# 48V-24V_Buck_Converter.net
KiCad netlist of a schematic drawn in Altium Designer
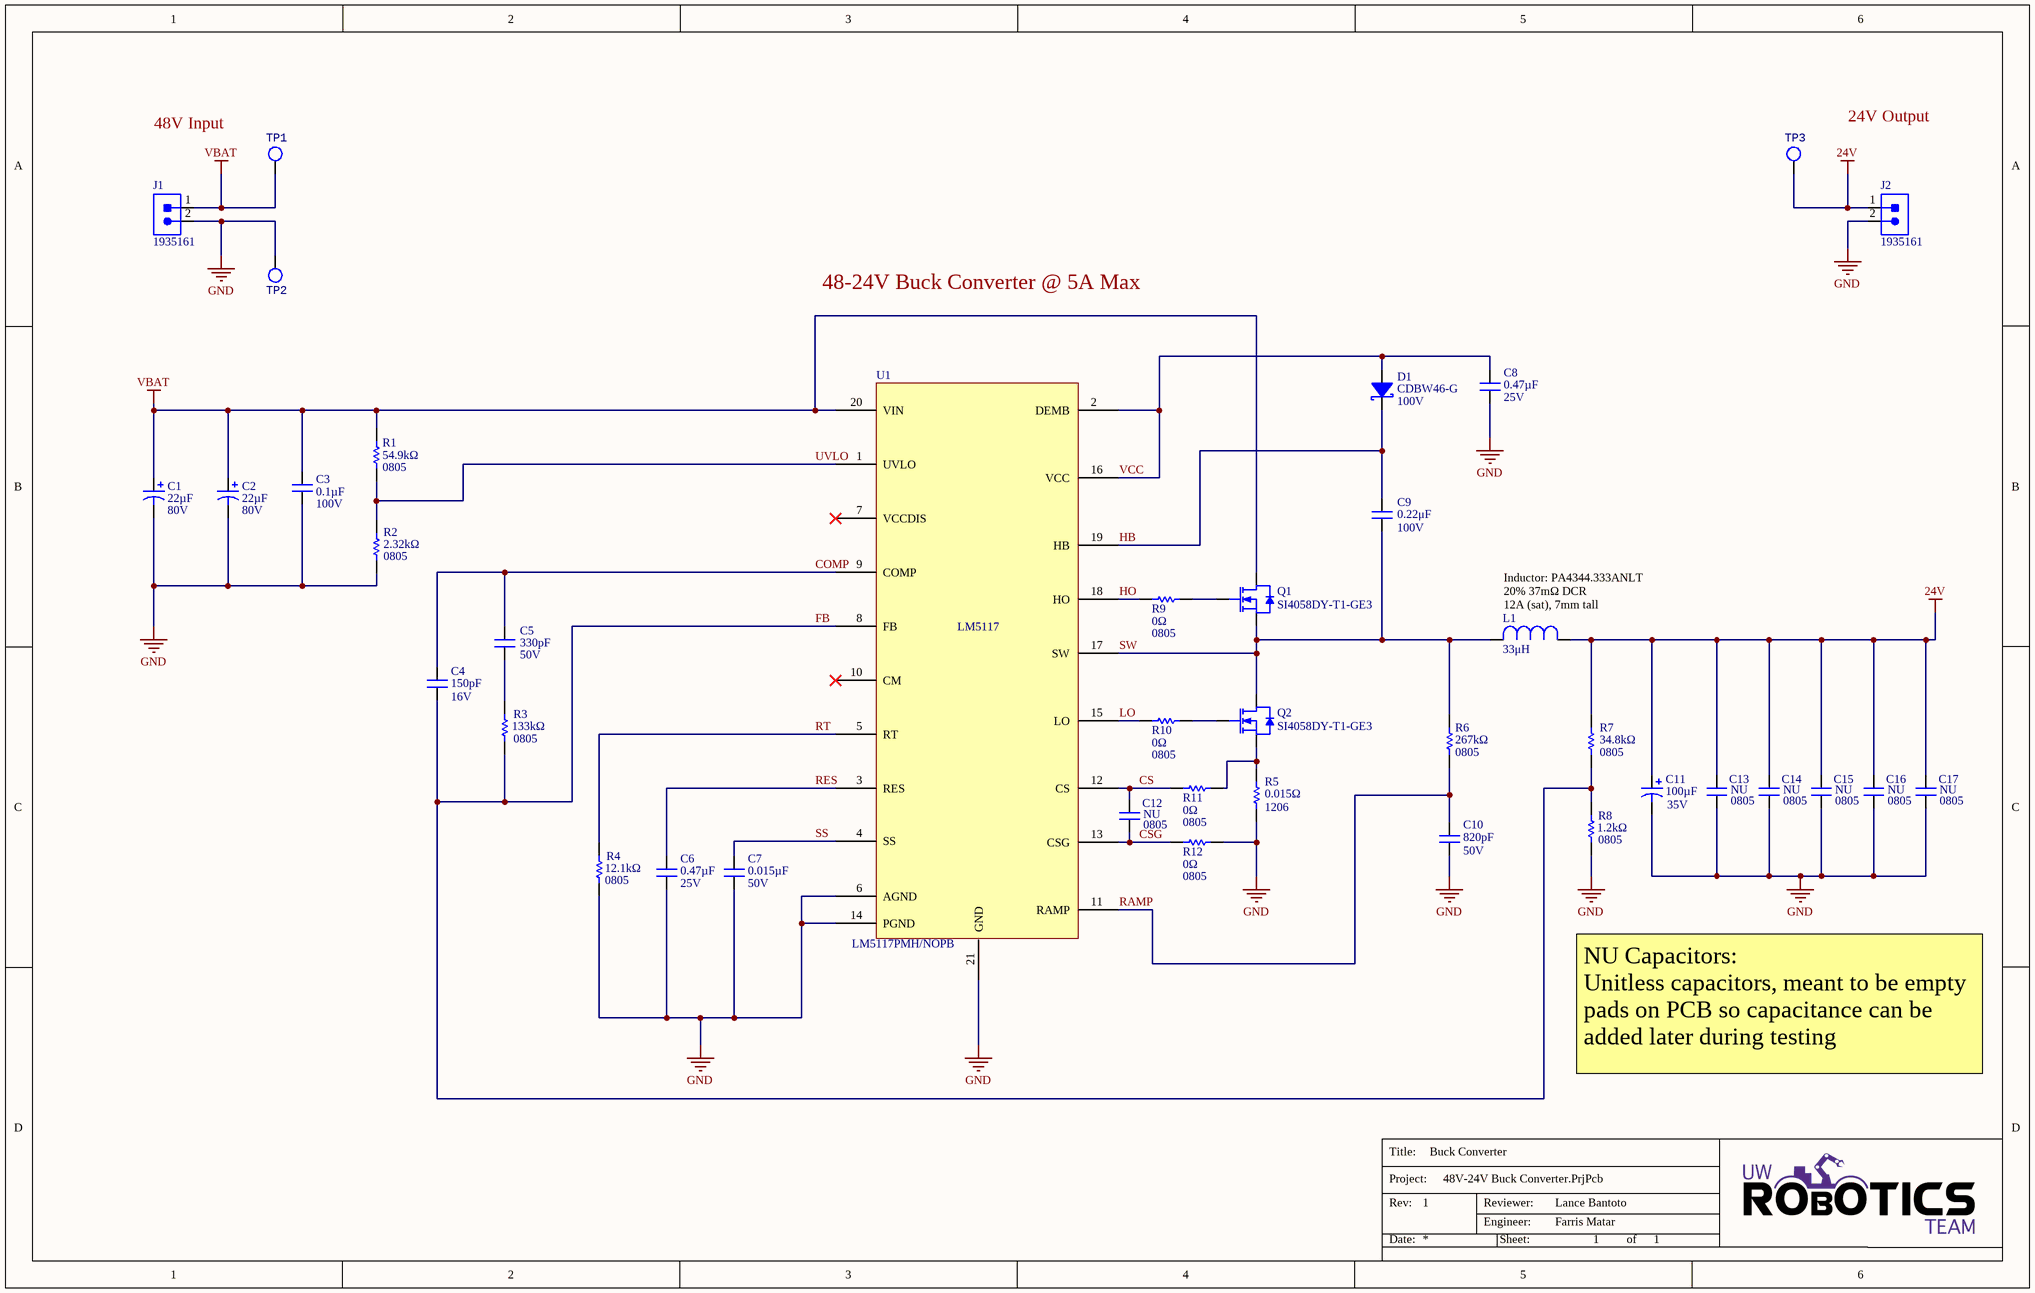
[diagram p0: 48V-24V Buck Converter.SchDoc]

(export (version "E")
  (design (tool "Eeschema 10.0.6"))
  (components
    (comp (ref "C1")
      (value "22µF")
      (footprint "RADIAL_KEMET_KN")
      (description "CAP ALUM POLY 22UF 20% 80V SMD")
      (fields (field (name "VOLTAGE RATING") "80V") (field (name "Comment") "CAP_22uF_80V_ALUM"))
      (libsource (lib "UWRT_Schematic_Library_2020") (part "CAP_22uF_80V_ALUM"))
    )
    (comp (ref "C2")
      (value "22µF")
      (footprint "RADIAL_KEMET_KN")
      (description "CAP ALUM POLY 22UF 20% 80V SMD")
      (fields (field (name "VOLTAGE RATING") "80V") (field (name "Comment") "CAP_22uF_80V_ALUM"))
      (libsource (lib "UWRT_Schematic_Library_2020") (part "CAP_22uF_80V_ALUM"))
    )
    (comp (ref "C3")
      (value "0.1µF")
      (footprint "CAP0805")
      (description "CAP CER 0.1UF 100V X7R 0805")
      (fields (field (name "VOLTAGE RATING") "100V") (field (name "Comment") "CAP_0.1uF_100V_0805"))
      (libsource (lib "UWRT_Schematic_Library_2020") (part "CAP_0.1uF_100V_0805"))
    )
    (comp (ref "C4")
      (value "150pF")
      (footprint "CAP0805")
      (description "CAP CER 150PF 16V X7R 0805")
      (fields (field (name "VOLTAGE RATING") "16V") (field (name "Comment") "CAP_150pF_16V_0805"))
      (libsource (lib "UWRT_Schematic_Library_2020") (part "CAP_150pF_16V_0805"))
    )
    (comp (ref "C5")
      (value "330pF")
      (footprint "CAP0805")
      (description "CAP CER 330PF 50V C0G/NPO 0805")
      (fields (field (name "VOLTAGE RATING") "50V") (field (name "Comment") "CAP_330pF_50V_0805"))
      (libsource (lib "UWRT_Schematic_Library_2020") (part "CAP_330pF_50V_0805"))
    )
    (comp (ref "C6")
      (value "0.47µF")
      (footprint "CAP0805")
      (description "CAP CER 0.47UF 25V X5R 0805")
      (fields (field (name "VOLTAGE RATING") "25V") (field (name "Comment") "CAP_0.47uF_25V_0805"))
      (libsource (lib "UWRT_Schematic_Library_2020") (part "CAP_0.47uF_25V_0805"))
    )
    (comp (ref "C7")
      (value "0.015µF")
      (footprint "CAP0805")
      (description "CAP CER 0.015UF 50V C0G 0805")
      (fields (field (name "VOLTAGE RATING") "50V") (field (name "Comment") "CAP_0.015uF_50V_0805"))
      (libsource (lib "UWRT_Schematic_Library_2020") (part "CAP_0.015uF_50V_0805"))
    )
    (comp (ref "C8")
      (value "0.47µF")
      (footprint "CAP0805")
      (description "CAP CER 0.47UF 25V X5R 0805")
      (fields (field (name "VOLTAGE RATING") "25V") (field (name "Comment") "CAP_0.47uF_25V_0805"))
      (libsource (lib "UWRT_Schematic_Library_2020") (part "CAP_0.47uF_25V_0805"))
    )
    (comp (ref "C9")
      (value "0.22μF")
      (footprint "CAP2012")
      (description "CAP CER 0.22UF 100V X7R 0805")
      (fields (field (name "VOLTAGE RATING") "100V") (field (name "Comment") "CAP_0.22uF_100V_0805"))
      (libsource (lib "UWRT_Schematic_Library_2020") (part "CAP_0.22uF_100V_0805"))
    )
    (comp (ref "C10")
      (value "820pF")
      (footprint "CAP0805")
      (description "CAP CER 820PF 50V C0G/NP0 0805")
      (fields (field (name "VOLTAGE RATING") "50V") (field (name "Comment") "CAP_820pF_50V_0805"))
      (libsource (lib "UWRT_Schematic_Library_2020") (part "CAP_820pF_50V_0805"))
    )
    (comp (ref "C11")
      (value "100µF")
      (footprint "RADIAL_CORNELL_D")
      (description "CAP ALUM 100UF 20% 35V SMD")
      (fields (field (name "VOLTAGE RATING") "35V") (field (name "Comment") "CAP_100uF_35V_ALUM"))
      (libsource (lib "UWRT_Schematic_Library_2020") (part "CAP_100uF_35V_ALUM"))
    )
    (comp (ref "C12")
      (value "NU")
      (footprint "CAP0805")
      (description "PLACEHOLDER CAPACITOR 0805")
      (fields (field (name "PACKAGE/FOOTPRINT") "0805") (field (name "Comment") "CAP_NU_0805"))
      (libsource (lib "UWRT_Schematic_Library_2020") (part "CAP_NU_0805"))
    )
    (comp (ref "C13")
      (value "NU")
      (footprint "CAP0805")
      (description "PLACEHOLDER CAPACITOR 0805")
      (fields (field (name "PACKAGE/FOOTPRINT") "0805") (field (name "Comment") "CAP_NU_0805"))
      (libsource (lib "UWRT_Schematic_Library_2020") (part "CAP_NU_0805"))
    )
    (comp (ref "C14")
      (value "NU")
      (footprint "CAP0805")
      (description "PLACEHOLDER CAPACITOR 0805")
      (fields (field (name "PACKAGE/FOOTPRINT") "0805") (field (name "Comment") "CAP_NU_0805"))
      (libsource (lib "UWRT_Schematic_Library_2020") (part "CAP_NU_0805"))
    )
    (comp (ref "C15")
      (value "NU")
      (footprint "CAP0805")
      (description "PLACEHOLDER CAPACITOR 0805")
      (fields (field (name "PACKAGE/FOOTPRINT") "0805") (field (name "Comment") "CAP_NU_0805"))
      (libsource (lib "UWRT_Schematic_Library_2020") (part "CAP_NU_0805"))
    )
    (comp (ref "C16")
      (value "NU")
      (footprint "CAP0805")
      (description "PLACEHOLDER CAPACITOR 0805")
      (fields (field (name "PACKAGE/FOOTPRINT") "0805") (field (name "Comment") "CAP_NU_0805"))
      (libsource (lib "UWRT_Schematic_Library_2020") (part "CAP_NU_0805"))
    )
    (comp (ref "C17")
      (value "NU")
      (footprint "CAP0805")
      (description "PLACEHOLDER CAPACITOR 0805")
      (fields (field (name "PACKAGE/FOOTPRINT") "0805") (field (name "Comment") "CAP_NU_0805"))
      (libsource (lib "UWRT_Schematic_Library_2020") (part "CAP_NU_0805"))
    )
    (comp (ref "D1")
      (value "DIO_SCHOTTKY_100V_150mA")
      (footprint "SOD-123_FLAT")
      (description "DIODE SCHOTTKY 100V 150MA SOD123")
      (fields (field (name "MANUFACTURER PART NUMBER 1") "CDBW46-G") (field (name "VR (MAX)") "100V"))
      (libsource (lib "UWRT_Schematic_Library_2020") (part "DIO_SCHOTTKY_100V_150mA"))
    )
    (comp (ref "J1")
      (value "CON_2POS_SCREW_TERM")
      (footprint "1935161")
      (description "TERM BLK 2POS SIDE ENTRY 5MM")
      (fields (field (name "MANUFACTURER PART NUMBER 1") "1935161"))
      (libsource (lib "UWRT_Schematic_Library_2020") (part "CON_2POS_SCREW_TERM"))
    )
    (comp (ref "J2")
      (value "CON_2POS_SCREW_TERM")
      (footprint "1935161")
      (description "TERM BLK 2POS SIDE ENTRY 5MM")
      (fields (field (name "MANUFACTURER PART NUMBER 1") "1935161"))
      (libsource (lib "") (part "CON_2POS_SCREW_TERM_1"))
    )
    (comp (ref "L1")
      (value "IND_33uH_12.0A")
      (footprint "IND_PULSE_PA4344")
      (description "FIXED IND 33UH 12A 37 MOHM SMD")
      (fields (field (name "INDUCTANCE") "33μH"))
      (libsource (lib "UWRT_Schematic_Library_2020") (part "IND_33uH_12.0A"))
    )
    (comp (ref "Q1")
      (value "NMOS_100V_10.3A")
      (footprint "8-SOIC_NMOS")
      (description "MOSFET N-CH 100V 10.3A 8SOIC")
      (fields (field (name "MANUFACTURER PART NUMBER 1") "SI4058DY-T1-GE3"))
      (libsource (lib "UWRT_Schematic_Library_2020") (part "NMOS_100V_10.3A"))
    )
    (comp (ref "Q2")
      (value "NMOS_100V_10.3A")
      (footprint "8-SOIC_NMOS")
      (description "MOSFET N-CH 100V 10.3A 8SOIC")
      (fields (field (name "MANUFACTURER PART NUMBER 1") "SI4058DY-T1-GE3"))
      (libsource (lib "UWRT_Schematic_Library_2020") (part "NMOS_100V_10.3A"))
    )
    (comp (ref "R1")
      (value "54.9kΩ")
      (footprint "RES0805")
      (description "RES SMD 54.9K OHM 1% 1/8W 0805")
      (fields (field (name "PACKAGE/FOOTPRINT") "0805") (field (name "Comment") "RES_54.9kΩ_0805_1%"))
      (libsource (lib "UWRT_Schematic_Library_2020") (part "RES_54.9kΩ_0805_1%"))
    )
    (comp (ref "R2")
      (value "2.32kΩ")
      (footprint "RES0805")
      (description "RES 2.32K OHM 1% 1/4W 0805")
      (fields (field (name "PACKAGE/FOOTPRINT") "0805") (field (name "Comment") "RES_2.32kΩ_0805_1%"))
      (libsource (lib "UWRT_Schematic_Library_2020") (part "RES_2.32kΩ_0805_1%"))
    )
    (comp (ref "R3")
      (value "133kΩ")
      (footprint "RES0805")
      (description "RES SMD 133K OHM 1% 1/8W 0805")
      (fields (field (name "PACKAGE/FOOTPRINT") "0805") (field (name "Comment") "RES_133kΩ_0805_1%"))
      (libsource (lib "UWRT_Schematic_Library_2020") (part "RES_133kΩ_0805_1%"))
    )
    (comp (ref "R4")
      (value "12.1kΩ")
      (footprint "RES0805")
      (description "RES 12.1K OHM 1% 1/4W 0805")
      (fields (field (name "PACKAGE/FOOTPRINT") "0805") (field (name "Comment") "RES_12.1kΩ_0805_1%"))
      (libsource (lib "UWRT_Schematic_Library_2020") (part "RES_12.1kΩ_0805_1%"))
    )
    (comp (ref "R5")
      (value "0.015Ω")
      (footprint "RES1206")
      (description "RES 0.015 OHM 1% 1/2W 1206")
      (fields (field (name "PACKAGE/FOOTPRINT") "1206") (field (name "Comment") "RES_0.015Ω_1206_1%"))
      (libsource (lib "UWRT_Schematic_Library_2020") (part "RES_0.015Ω_1206_1%"))
    )
    (comp (ref "R6")
      (value "267kΩ")
      (footprint "RES0805")
      (description "RES SMD 267K OHM 1% 1/8W 0805")
      (fields (field (name "PACKAGE/FOOTPRINT") "0805") (field (name "Comment") "RES_267kΩ_0805_1%"))
      (libsource (lib "UWRT_Schematic_Library_2020") (part "RES_267kΩ_0805_1%"))
    )
    (comp (ref "R7")
      (value "34.8kΩ")
      (footprint "RES0805")
      (description "RES 34.8K OHM 1% 1/8W 0805")
      (fields (field (name "PACKAGE/FOOTPRINT") "0805") (field (name "Comment") "RES_34.8kΩ_0805_1%"))
      (libsource (lib "UWRT_Schematic_Library_2020") (part "RES_34.8kΩ_0805_1%"))
    )
    (comp (ref "R8")
      (value "1.2kΩ")
      (footprint "RES0805")
      (description "RES SMD 1.2K OHM 1% 1/8W 0805")
      (fields (field (name "PACKAGE/FOOTPRINT") "0805") (field (name "Comment") "RES_1.2kΩ_0805"))
      (libsource (lib "UWRT_Schematic_Library_2020") (part "RES_1.2kΩ_0805_1%"))
    )
    (comp (ref "R9")
      (value "0Ω")
      (footprint "RES0805")
      (description "RES 0 OHM JUMPER 1/8W 0805")
      (fields
        (field (name "PACKAGE/FOOTPRINT") "0805")
        (field (name "LCSC PART #") "C17477")
        (field (name "Comment") "RES_0Ω_0805")
      )
      (libsource (lib "UWRT_Schematic_Library_2020") (part "RES_0Ω_0805"))
    )
    (comp (ref "R10")
      (value "0Ω")
      (footprint "RES0805")
      (description "RES 0 OHM JUMPER 1/8W 0805")
      (fields
        (field (name "PACKAGE/FOOTPRINT") "0805")
        (field (name "LCSC PART #") "C17477")
        (field (name "Comment") "RES_0Ω_0805")
      )
      (libsource (lib "UWRT_Schematic_Library_2020") (part "RES_0Ω_0805"))
    )
    (comp (ref "R11")
      (value "0Ω")
      (footprint "RES0805")
      (description "RES 0 OHM JUMPER 1/8W 0805")
      (fields
        (field (name "PACKAGE/FOOTPRINT") "0805")
        (field (name "LCSC PART #") "C17477")
        (field (name "Comment") "RES_0Ω_0805")
      )
      (libsource (lib "UWRT_Schematic_Library_2020") (part "RES_0Ω_0805"))
    )
    (comp (ref "R12")
      (value "0Ω")
      (footprint "RES0805")
      (description "RES 0 OHM JUMPER 1/8W 0805")
      (fields
        (field (name "PACKAGE/FOOTPRINT") "0805")
        (field (name "LCSC PART #") "C17477")
        (field (name "Comment") "RES_0Ω_0805")
      )
      (libsource (lib "UWRT_Schematic_Library_2020") (part "RES_0Ω_0805"))
    )
    (comp (ref "TP1")
      (value "TESTPOINT_LOOP")
      (footprint "TESTPOINT_LOOP")
      (description "TESTPOINT THRUHOLE")
      (libsource (lib "UWRT_Schematic_Library_2020") (part "TESTPOINT_LOOP"))
    )
    (comp (ref "TP2")
      (value "TESTPOINT_LOOP")
      (footprint "TESTPOINT_LOOP")
      (description "TESTPOINT THRUHOLE")
      (libsource (lib "UWRT_Schematic_Library_2020") (part "TESTPOINT_LOOP"))
    )
    (comp (ref "TP3")
      (value "TESTPOINT_LOOP")
      (footprint "TESTPOINT_LOOP")
      (description "TESTPOINT THRUHOLE")
      (libsource (lib "UWRT_Schematic_Library_2020") (part "TESTPOINT_LOOP"))
    )
    (comp (ref "U1")
      (value "BUCK_LM5117PWP")
      (footprint "HTSSOP")
      (description "IC REG CTRLR BUCK 20TSSOP")
      (fields (field (name "MANUFACTURER PART NUMBER 1") "LM5117PMH/NOPB"))
      (libsource (lib "UWRT_Schematic_Library_2020") (part "BUCK_LM5117PWP"))
    )
  )
  (nets
    (net (code "1") (name "/COMP") (class "Default")
      (node (ref "C4") (pin "2") (pinfunction "2_2") (pintype "passive"))
      (node (ref "C5") (pin "2") (pinfunction "2_2") (pintype "passive"))
      (node (ref "U1") (pin "9") (pinfunction "COMP_9") (pintype "passive"))
    )
    (net (code "2") (name "/CS") (class "Default")
      (node (ref "C12") (pin "2") (pinfunction "2_2") (pintype "passive"))
      (node (ref "R11") (pin "1") (pinfunction "1_1") (pintype "passive"))
      (node (ref "U1") (pin "12") (pinfunction "CS_12") (pintype "passive"))
    )
    (net (code "3") (name "/CSG") (class "Default")
      (node (ref "C12") (pin "1") (pinfunction "1_1") (pintype "passive"))
      (node (ref "R12") (pin "1") (pinfunction "1_1") (pintype "passive"))
      (node (ref "U1") (pin "13") (pinfunction "CSG_13") (pintype "passive"))
    )
    (net (code "4") (name "/FB") (class "Default")
      (node (ref "C4") (pin "1") (pinfunction "1_1") (pintype "passive"))
      (node (ref "R3") (pin "1") (pinfunction "1_1") (pintype "passive"))
      (node (ref "R7") (pin "1") (pinfunction "1_1") (pintype "passive"))
      (node (ref "R8") (pin "2") (pinfunction "2_2") (pintype "passive"))
      (node (ref "U1") (pin "8") (pinfunction "FB_8") (pintype "passive"))
    )
    (net (code "5") (name "/HB") (class "Default")
      (node (ref "C9") (pin "2") (pinfunction "2_2") (pintype "passive"))
      (node (ref "D1") (pin "2") (pinfunction "Cathode_2") (pintype "passive"))
      (node (ref "U1") (pin "19") (pinfunction "HB_19") (pintype "passive"))
    )
    (net (code "6") (name "/HO") (class "Default")
      (node (ref "R9") (pin "1") (pinfunction "1_1") (pintype "passive"))
      (node (ref "U1") (pin "18") (pinfunction "HO_18") (pintype "passive"))
    )
    (net (code "7") (name "/LO") (class "Default")
      (node (ref "R10") (pin "1") (pinfunction "1_1") (pintype "passive"))
      (node (ref "U1") (pin "15") (pinfunction "LO_15") (pintype "passive"))
    )
    (net (code "8") (name "/RAMP") (class "Default")
      (node (ref "C10") (pin "2") (pinfunction "2_2") (pintype "passive"))
      (node (ref "R6") (pin "1") (pinfunction "1_1") (pintype "passive"))
      (node (ref "U1") (pin "11") (pinfunction "RAMP_11") (pintype "passive"))
    )
    (net (code "9") (name "/RES") (class "Default")
      (node (ref "C6") (pin "2") (pinfunction "2_2") (pintype "passive"))
      (node (ref "U1") (pin "3") (pinfunction "RES_3") (pintype "passive"))
    )
    (net (code "10") (name "/RT") (class "Default")
      (node (ref "R4") (pin "2") (pinfunction "2_2") (pintype "passive"))
      (node (ref "U1") (pin "5") (pinfunction "RT_5") (pintype "passive"))
    )
    (net (code "11") (name "/SS") (class "Default")
      (node (ref "C7") (pin "2") (pinfunction "2_2") (pintype "passive"))
      (node (ref "U1") (pin "4") (pinfunction "SS_4") (pintype "passive"))
    )
    (net (code "12") (name "/SW") (class "Default")
      (node (ref "C9") (pin "1") (pinfunction "1_1") (pintype "passive"))
      (node (ref "L1") (pin "2") (pinfunction "2_2") (pintype "passive"))
      (node (ref "Q1") (pin "2") (pinfunction "Source_2") (pintype "passive"))
      (node (ref "Q2") (pin "3") (pinfunction "Drain_3") (pintype "passive"))
      (node (ref "R6") (pin "2") (pinfunction "2_2") (pintype "passive"))
      (node (ref "U1") (pin "17") (pinfunction "SW_17") (pintype "passive"))
    )
    (net (code "13") (name "/UVLO") (class "Default")
      (node (ref "R1") (pin "1") (pinfunction "1_1") (pintype "passive"))
      (node (ref "R2") (pin "2") (pinfunction "2_2") (pintype "passive"))
      (node (ref "U1") (pin "1") (pinfunction "UVLO_1") (pintype "passive"))
    )
    (net (code "14") (name "/VCC") (class "Default")
      (node (ref "C8") (pin "2") (pinfunction "2_2") (pintype "passive"))
      (node (ref "D1") (pin "1") (pinfunction "Anode_1") (pintype "passive"))
      (node (ref "U1") (pin "16") (pinfunction "VCC_16") (pintype "passive"))
      (node (ref "U1") (pin "2") (pinfunction "DEMB_2") (pintype "passive"))
    )
    (net (code "15") (name "24V") (class "Default")
      (node (ref "C11") (pin "1") (pinfunction "1_1") (pintype "passive"))
      (node (ref "C13") (pin "2") (pinfunction "2_2") (pintype "passive"))
      (node (ref "C14") (pin "2") (pinfunction "2_2") (pintype "passive"))
      (node (ref "C15") (pin "2") (pinfunction "2_2") (pintype "passive"))
      (node (ref "C16") (pin "2") (pinfunction "2_2") (pintype "passive"))
      (node (ref "C17") (pin "2") (pinfunction "2_2") (pintype "passive"))
      (node (ref "J2") (pin "1") (pinfunction "1_1") (pintype "passive"))
      (node (ref "L1") (pin "1") (pinfunction "1_1") (pintype "passive"))
      (node (ref "R7") (pin "2") (pinfunction "2_2") (pintype "passive"))
      (node (ref "TP3") (pin "1") (pintype "passive"))
    )
    (net (code "16") (name "GND") (class "Default")
      (node (ref "C1") (pin "2") (pinfunction "2_2") (pintype "passive"))
      (node (ref "C10") (pin "1") (pinfunction "1_1") (pintype "passive"))
      (node (ref "C11") (pin "2") (pinfunction "2_2") (pintype "passive"))
      (node (ref "C13") (pin "1") (pinfunction "1_1") (pintype "passive"))
      (node (ref "C14") (pin "1") (pinfunction "1_1") (pintype "passive"))
      (node (ref "C15") (pin "1") (pinfunction "1_1") (pintype "passive"))
      (node (ref "C16") (pin "1") (pinfunction "1_1") (pintype "passive"))
      (node (ref "C17") (pin "1") (pinfunction "1_1") (pintype "passive"))
      (node (ref "C2") (pin "2") (pinfunction "2_2") (pintype "passive"))
      (node (ref "C3") (pin "1") (pinfunction "1_1") (pintype "passive"))
      (node (ref "C6") (pin "1") (pinfunction "1_1") (pintype "passive"))
      (node (ref "C7") (pin "1") (pinfunction "1_1") (pintype "passive"))
      (node (ref "C8") (pin "1") (pinfunction "1_1") (pintype "passive"))
      (node (ref "J1") (pin "2") (pinfunction "2_2") (pintype "passive"))
      (node (ref "J2") (pin "2") (pinfunction "2_2") (pintype "passive"))
      (node (ref "R12") (pin "2") (pinfunction "2_2") (pintype "passive"))
      (node (ref "R2") (pin "1") (pinfunction "1_1") (pintype "passive"))
      (node (ref "R4") (pin "1") (pinfunction "1_1") (pintype "passive"))
      (node (ref "R5") (pin "1") (pinfunction "1_1") (pintype "passive"))
      (node (ref "R8") (pin "1") (pinfunction "1_1") (pintype "passive"))
      (node (ref "TP2") (pin "1") (pintype "passive"))
      (node (ref "U1") (pin "14") (pinfunction "PGND_14") (pintype "passive"))
      (node (ref "U1") (pin "21") (pinfunction "GND_21") (pintype "passive"))
      (node (ref "U1") (pin "6") (pinfunction "AGND_6") (pintype "passive"))
    )
    (net (code "17") (name "Net-(C5-Pad1)") (class "Default")
      (node (ref "C5") (pin "1") (pinfunction "1_1") (pintype "passive"))
      (node (ref "R3") (pin "2") (pinfunction "2_2") (pintype "passive"))
    )
    (net (code "18") (name "Net-(Q1-Gate)") (class "Default")
      (node (ref "Q1") (pin "1") (pinfunction "Gate_1") (pintype "passive"))
      (node (ref "R9") (pin "2") (pinfunction "2_2") (pintype "passive"))
    )
    (net (code "19") (name "Net-(Q2-Gate)") (class "Default")
      (node (ref "Q2") (pin "1") (pinfunction "Gate_1") (pintype "passive"))
      (node (ref "R10") (pin "2") (pinfunction "2_2") (pintype "passive"))
    )
    (net (code "20") (name "Net-(Q2-Source)") (class "Default")
      (node (ref "Q2") (pin "2") (pinfunction "Source_2") (pintype "passive"))
      (node (ref "R11") (pin "2") (pinfunction "2_2") (pintype "passive"))
      (node (ref "R5") (pin "2") (pinfunction "2_2") (pintype "passive"))
    )
    (net (code "21") (name "VBAT") (class "Default")
      (node (ref "C1") (pin "1") (pinfunction "1_1") (pintype "passive"))
      (node (ref "C2") (pin "1") (pinfunction "1_1") (pintype "passive"))
      (node (ref "C3") (pin "2") (pinfunction "2_2") (pintype "passive"))
      (node (ref "J1") (pin "1") (pinfunction "1_1") (pintype "passive"))
      (node (ref "Q1") (pin "3") (pinfunction "Drain_3") (pintype "passive"))
      (node (ref "R1") (pin "2") (pinfunction "2_2") (pintype "passive"))
      (node (ref "TP1") (pin "1") (pintype "passive"))
      (node (ref "U1") (pin "20") (pinfunction "VIN_20") (pintype "passive"))
    )
    (net (code "22") (name "unconnected-(U1-CM-Pad10)") (class "Default")
      (node (ref "U1") (pin "10") (pinfunction "CM_10") (pintype "passive+no_connect"))
    )
    (net (code "23") (name "unconnected-(U1-VCCDIS-Pad7)") (class "Default")
      (node (ref "U1") (pin "7") (pinfunction "VCCDIS_7") (pintype "passive+no_connect"))
    )
  )
)
